# Sheet4.net
KiCad netlist of a schematic drawn in Altium Designer
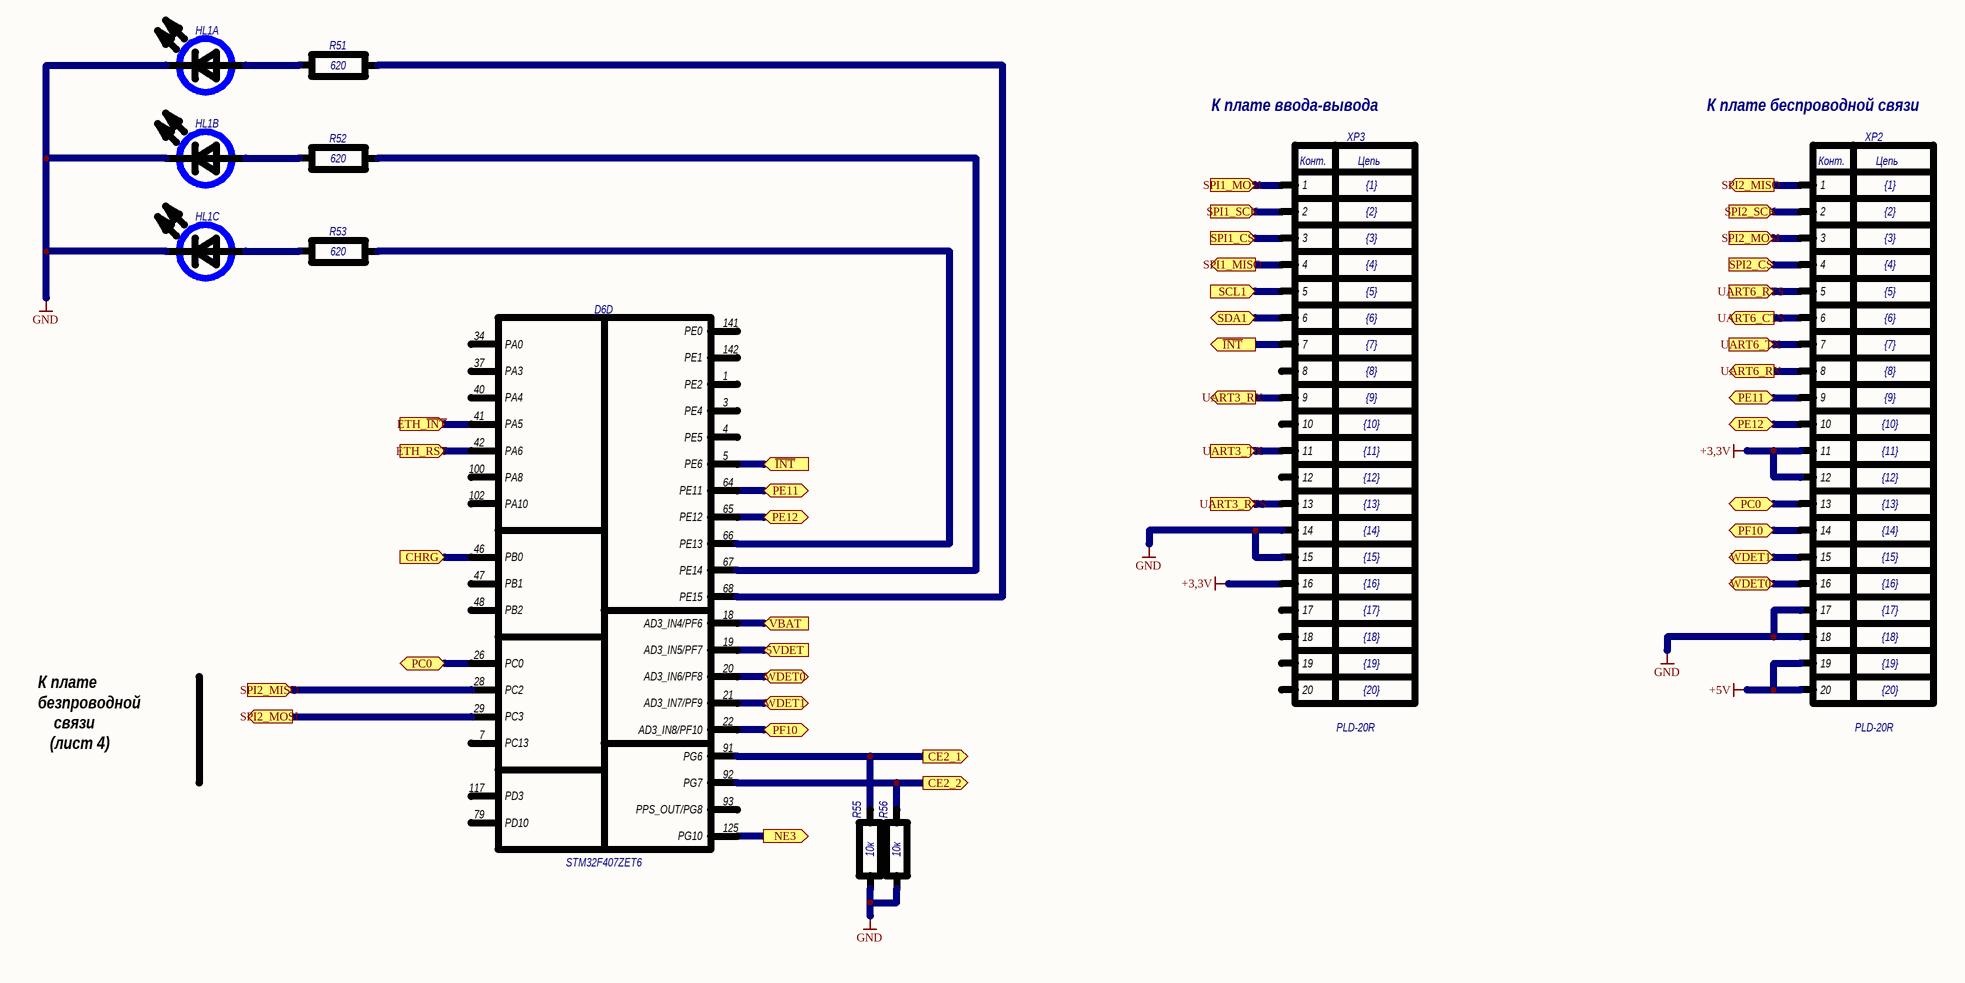
[diagram p0: Sheet4.SCHDOC]

(export (version "E")
  (design (tool "Eeschema 10.0.6"))
  (components
    (comp (ref "D6")
      (value "STM32F407ZET6")
      (footprint "LQFP-144")
      (libsource (lib "*") (part "STM32F407ZET6"))
    )
    (comp (ref "HL1")
      (value "L-7104SA-3GD")
      (footprint "L-7104SA-3GD")
      (description "{Description}")
      (libsource (lib "") (part "L-7104SA-3GD_1"))
    )
    (comp (ref "R51")
      (value "620")
      (footprint "0805")
      (description "РЕЗИСТОР")
      (fields (field (name "Comment") "Р0805"))
      (libsource (lib "*") (part "Р0805"))
    )
    (comp (ref "R52")
      (value "620")
      (footprint "0805")
      (description "РЕЗИСТОР")
      (fields (field (name "Comment") "Р0805"))
      (libsource (lib "*") (part "Р0805"))
    )
    (comp (ref "R53")
      (value "620")
      (footprint "0805")
      (description "РЕЗИСТОР")
      (fields (field (name "Comment") "Р0805"))
      (libsource (lib "*") (part "Р0805"))
    )
    (comp (ref "R55")
      (value "Р0805")
      (footprint "0805")
      (description "РЕЗИСТОР")
      (fields (field (name "ALTIUM_UNNAMED_1") "10к"))
      (libsource (lib "*") (part "Р0805"))
    )
    (comp (ref "R56")
      (value "Р0805")
      (footprint "0805")
      (description "РЕЗИСТОР")
      (fields (field (name "ALTIUM_UNNAMED_1") "10к"))
      (libsource (lib "*") (part "Р0805"))
    )
    (comp (ref "XP2")
      (value "PLD-20R")
      (footprint "PLD-20R")
      (description "{Description}")
      (fields
        (field (name "18") "{18}")
        (field (name "15") "{15}")
        (field (name "12") "{12}")
        (field (name "9") "{9}")
        (field (name "6") "{6}")
        (field (name "3") "{3}")
        (field (name "1") "{1}")
        (field (name "19") "{19}")
        (field (name "16") "{16}")
        (field (name "20") "{20}")
        (field (name "17") "{17}")
        (field (name "13") "{13}")
        (field (name "10") "{10}")
        (field (name "14") "{14}")
        (field (name "11") "{11}")
        (field (name "7") "{7}")
        (field (name "4") "{4}")
        (field (name "8") "{8}")
        (field (name "5") "{5}")
        (field (name "2") "{2}")
      )
      (libsource (lib "*") (part "PLD-20R"))
    )
    (comp (ref "XP3")
      (value "PLD-20R")
      (footprint "PLD-20R")
      (description "{Description}")
      (fields
        (field (name "18") "{18}")
        (field (name "15") "{15}")
        (field (name "12") "{12}")
        (field (name "9") "{9}")
        (field (name "6") "{6}")
        (field (name "3") "{3}")
        (field (name "1") "{1}")
        (field (name "19") "{19}")
        (field (name "16") "{16}")
        (field (name "20") "{20}")
        (field (name "17") "{17}")
        (field (name "13") "{13}")
        (field (name "10") "{10}")
        (field (name "14") "{14}")
        (field (name "11") "{11}")
        (field (name "7") "{7}")
        (field (name "4") "{4}")
        (field (name "8") "{8}")
        (field (name "5") "{5}")
        (field (name "2") "{2}")
      )
      (libsource (lib "*") (part "PLD-20R"))
    )
  )
  (nets
    (net (code "1") (name "+3,3V") (class "Default")
      (node (ref "XP2") (pin "11") (pinfunction "11_11") (pintype "passive"))
      (node (ref "XP2") (pin "12") (pinfunction "12_12") (pintype "passive"))
      (node (ref "XP3") (pin "16") (pinfunction "16_16") (pintype "passive"))
    )
    (net (code "2") (name "+5V") (class "Default")
      (node (ref "XP2") (pin "19") (pinfunction "19_19") (pintype "passive"))
      (node (ref "XP2") (pin "20") (pinfunction "20_20") (pintype "passive"))
    )
    (net (code "3") (name "/5VDET") (class "Default")
      (node (ref "D6") (pin "19") (pinfunction "AD3_IN5/PF7_19") (pintype "passive"))
    )
    (net (code "4") (name "/CE2_1") (class "Default")
      (node (ref "D6") (pin "91") (pinfunction "PG6_91") (pintype "passive"))
      (node (ref "R55") (pin "2") (pinfunction "2_2") (pintype "passive"))
    )
    (net (code "5") (name "/CE2_2") (class "Default")
      (node (ref "D6") (pin "92") (pinfunction "PG7_92") (pintype "passive"))
      (node (ref "R56") (pin "2") (pinfunction "2_2") (pintype "passive"))
    )
    (net (code "6") (name "/CHRG") (class "Default")
      (node (ref "D6") (pin "46") (pinfunction "PB0_46") (pintype "passive"))
    )
    (net (code "7") (name "/ETH_RST") (class "Default")
      (node (ref "D6") (pin "42") (pinfunction "PA6_42") (pintype "passive"))
    )
    (net (code "8") (name "/ETH_~{INT}") (class "Default")
      (node (ref "D6") (pin "41") (pinfunction "PA5_41") (pintype "passive"))
    )
    (net (code "9") (name "/NE3") (class "Default")
      (node (ref "D6") (pin "125") (pinfunction "PG10_125") (pintype "passive"))
    )
    (net (code "10") (name "/PC0") (class "Default")
      (node (ref "D6") (pin "26") (pinfunction "PC0_26") (pintype "passive"))
      (node (ref "XP2") (pin "13") (pinfunction "13_13") (pintype "passive"))
    )
    (net (code "11") (name "/PE11") (class "Default")
      (node (ref "D6") (pin "64") (pinfunction "PE11_64") (pintype "passive"))
      (node (ref "XP2") (pin "9") (pinfunction "9_9") (pintype "passive"))
    )
    (net (code "12") (name "/PE12") (class "Default")
      (node (ref "D6") (pin "65") (pinfunction "PE12_65") (pintype "passive"))
      (node (ref "XP2") (pin "10") (pinfunction "10_10") (pintype "passive"))
    )
    (net (code "13") (name "/PF10") (class "Default")
      (node (ref "D6") (pin "22") (pinfunction "AD3_IN8/PF10_22") (pintype "passive"))
      (node (ref "XP2") (pin "14") (pinfunction "14_14") (pintype "passive"))
    )
    (net (code "14") (name "/SCL1") (class "Default")
      (node (ref "XP3") (pin "5") (pinfunction "5_5") (pintype "passive"))
    )
    (net (code "15") (name "/SDA1") (class "Default")
      (node (ref "XP3") (pin "6") (pinfunction "6_6") (pintype "passive"))
    )
    (net (code "16") (name "/SPI1_CS") (class "Default")
      (node (ref "XP3") (pin "3") (pinfunction "3_3") (pintype "passive"))
    )
    (net (code "17") (name "/SPI1_MISO") (class "Default")
      (node (ref "XP3") (pin "4") (pinfunction "4_4") (pintype "passive"))
    )
    (net (code "18") (name "/SPI1_MOSI") (class "Default")
      (node (ref "XP3") (pin "1") (pinfunction "1_1") (pintype "passive"))
    )
    (net (code "19") (name "/SPI1_SCK") (class "Default")
      (node (ref "XP3") (pin "2") (pinfunction "2_2") (pintype "passive"))
    )
    (net (code "20") (name "/SPI2_CS") (class "Default")
      (node (ref "XP2") (pin "4") (pinfunction "4_4") (pintype "passive"))
    )
    (net (code "21") (name "/SPI2_MISO") (class "Default")
      (node (ref "D6") (pin "28") (pinfunction "PC2_28") (pintype "passive"))
      (node (ref "XP2") (pin "1") (pinfunction "1_1") (pintype "passive"))
    )
    (net (code "22") (name "/SPI2_MOSI") (class "Default")
      (node (ref "D6") (pin "29") (pinfunction "PC3_29") (pintype "passive"))
      (node (ref "XP2") (pin "3") (pinfunction "3_3") (pintype "passive"))
    )
    (net (code "23") (name "/SPI2_SCK") (class "Default")
      (node (ref "XP2") (pin "2") (pinfunction "2_2") (pintype "passive"))
    )
    (net (code "24") (name "/UART3_RTS") (class "Default")
      (node (ref "XP3") (pin "13") (pinfunction "13_13") (pintype "passive"))
    )
    (net (code "25") (name "/UART3_RX") (class "Default")
      (node (ref "XP3") (pin "9") (pinfunction "9_9") (pintype "passive"))
    )
    (net (code "26") (name "/UART3_TX") (class "Default")
      (node (ref "XP3") (pin "11") (pinfunction "11_11") (pintype "passive"))
    )
    (net (code "27") (name "/UART6_CTS") (class "Default")
      (node (ref "XP2") (pin "6") (pinfunction "6_6") (pintype "passive"))
    )
    (net (code "28") (name "/UART6_RTS") (class "Default")
      (node (ref "XP2") (pin "5") (pinfunction "5_5") (pintype "passive"))
    )
    (net (code "29") (name "/UART6_RX") (class "Default")
      (node (ref "XP2") (pin "8") (pinfunction "8_8") (pintype "passive"))
    )
    (net (code "30") (name "/UART6_TX") (class "Default")
      (node (ref "XP2") (pin "7") (pinfunction "7_7") (pintype "passive"))
    )
    (net (code "31") (name "/VBAT") (class "Default")
      (node (ref "D6") (pin "18") (pinfunction "AD3_IN4/PF6_18") (pintype "passive"))
    )
    (net (code "32") (name "/WDET0") (class "Default")
      (node (ref "D6") (pin "20") (pinfunction "AD3_IN6/PF8_20") (pintype "passive"))
      (node (ref "XP2") (pin "16") (pinfunction "16_16") (pintype "passive"))
    )
    (net (code "33") (name "/WDET1") (class "Default")
      (node (ref "D6") (pin "21") (pinfunction "AD3_IN7/PF9_21") (pintype "passive"))
      (node (ref "XP2") (pin "15") (pinfunction "15_15") (pintype "passive"))
    )
    (net (code "34") (name "/~{INT}") (class "Default")
      (node (ref "D6") (pin "5") (pinfunction "PE6_5") (pintype "passive"))
      (node (ref "XP3") (pin "7") (pinfunction "7_7") (pintype "passive"))
    )
    (net (code "35") (name "GND") (class "Default")
      (node (ref "HL1") (pin "2") (pinfunction "2_2") (pintype "passive"))
      (node (ref "HL1") (pin "4") (pinfunction "2_4") (pintype "passive"))
      (node (ref "HL1") (pin "6") (pinfunction "2_6") (pintype "passive"))
      (node (ref "R55") (pin "1") (pinfunction "1_1") (pintype "passive"))
      (node (ref "R56") (pin "1") (pinfunction "1_1") (pintype "passive"))
      (node (ref "XP2") (pin "17") (pinfunction "17_17") (pintype "passive"))
      (node (ref "XP2") (pin "18") (pinfunction "18_18") (pintype "passive"))
      (node (ref "XP3") (pin "14") (pinfunction "14_14") (pintype "passive"))
      (node (ref "XP3") (pin "15") (pinfunction "15_15") (pintype "passive"))
    )
    (net (code "36") (name "Net-(D6D-PE13)") (class "Default")
      (node (ref "D6") (pin "66") (pinfunction "PE13_66") (pintype "passive"))
      (node (ref "R53") (pin "2") (pinfunction "2_2") (pintype "passive"))
    )
    (net (code "37") (name "Net-(D6D-PE14)") (class "Default")
      (node (ref "D6") (pin "67") (pinfunction "PE14_67") (pintype "passive"))
      (node (ref "R52") (pin "2") (pinfunction "2_2") (pintype "passive"))
    )
    (net (code "38") (name "Net-(D6D-PE15)") (class "Default")
      (node (ref "D6") (pin "68") (pinfunction "PE15_68") (pintype "passive"))
      (node (ref "R51") (pin "2") (pinfunction "2_2") (pintype "passive"))
    )
    (net (code "39") (name "Net-(HL1-Pad1)") (class "Default")
      (node (ref "HL1") (pin "1") (pinfunction "1_1") (pintype "passive"))
      (node (ref "R51") (pin "1") (pinfunction "1_1") (pintype "passive"))
    )
    (net (code "40") (name "Net-(HL1B-1)") (class "Default")
      (node (ref "HL1") (pin "3") (pinfunction "1_3") (pintype "passive"))
      (node (ref "R52") (pin "1") (pinfunction "1_1") (pintype "passive"))
    )
    (net (code "41") (name "Net-(HL1C-1)") (class "Default")
      (node (ref "HL1") (pin "5") (pinfunction "1_5") (pintype "passive"))
      (node (ref "R53") (pin "1") (pinfunction "1_1") (pintype "passive"))
    )
    (net (code "42") (name "unconnected-(D6-Pad49)") (class "Default")
      (node (ref "D6") (pin "49") (pintype "passive"))
    )
    (net (code "43") (name "unconnected-(D6D-PA0-Pad34)") (class "Default")
      (node (ref "D6") (pin "34") (pinfunction "PA0_34") (pintype "passive"))
    )
    (net (code "44") (name "unconnected-(D6D-PA3-Pad37)") (class "Default")
      (node (ref "D6") (pin "37") (pinfunction "PA3_37") (pintype "passive"))
    )
    (net (code "45") (name "unconnected-(D6D-PA4-Pad40)") (class "Default")
      (node (ref "D6") (pin "40") (pinfunction "PA4_40") (pintype "passive"))
    )
    (net (code "46") (name "unconnected-(D6D-PA8-Pad100)") (class "Default")
      (node (ref "D6") (pin "100") (pinfunction "PA8_100") (pintype "passive"))
    )
    (net (code "47") (name "unconnected-(D6D-PA10-Pad102)") (class "Default")
      (node (ref "D6") (pin "102") (pinfunction "PA10_102") (pintype "passive"))
    )
    (net (code "48") (name "unconnected-(D6D-PB1-Pad47)") (class "Default")
      (node (ref "D6") (pin "47") (pinfunction "PB1_47") (pintype "passive"))
    )
    (net (code "49") (name "unconnected-(D6D-PB2-Pad48)") (class "Default")
      (node (ref "D6") (pin "48") (pinfunction "PB2_48") (pintype "passive"))
    )
    (net (code "50") (name "unconnected-(D6D-PC13-Pad7)") (class "Default")
      (node (ref "D6") (pin "7") (pinfunction "PC13_7") (pintype "passive"))
    )
    (net (code "51") (name "unconnected-(D6D-PD3-Pad117)") (class "Default")
      (node (ref "D6") (pin "117") (pinfunction "PD3_117") (pintype "passive"))
    )
    (net (code "52") (name "unconnected-(D6D-PD10-Pad79)") (class "Default")
      (node (ref "D6") (pin "79") (pinfunction "PD10_79") (pintype "passive"))
    )
    (net (code "53") (name "unconnected-(D6D-PE0-Pad141)") (class "Default")
      (node (ref "D6") (pin "141") (pinfunction "PE0_141") (pintype "passive"))
    )
    (net (code "54") (name "unconnected-(D6D-PE1-Pad142)") (class "Default")
      (node (ref "D6") (pin "142") (pinfunction "PE1_142") (pintype "passive"))
    )
    (net (code "55") (name "unconnected-(D6D-PE2-Pad1)") (class "Default")
      (node (ref "D6") (pin "1") (pinfunction "PE2_1") (pintype "passive"))
    )
    (net (code "56") (name "unconnected-(D6D-PE4-Pad3)") (class "Default")
      (node (ref "D6") (pin "3") (pinfunction "PE4_3") (pintype "passive"))
    )
    (net (code "57") (name "unconnected-(D6D-PE5-Pad4)") (class "Default")
      (node (ref "D6") (pin "4") (pinfunction "PE5_4") (pintype "passive"))
    )
    (net (code "58") (name "unconnected-(D6D-PPS_OUT{slash}PG8-Pad93)") (class "Default")
      (node (ref "D6") (pin "93") (pinfunction "PPS_OUT/PG8_93") (pintype "passive"))
    )
    (net (code "59") (name "unconnected-(XP3-Pad8)") (class "Default")
      (node (ref "XP3") (pin "8") (pinfunction "8_8") (pintype "passive"))
    )
    (net (code "60") (name "unconnected-(XP3-Pad10)") (class "Default")
      (node (ref "XP3") (pin "10") (pinfunction "10_10") (pintype "passive"))
    )
    (net (code "61") (name "unconnected-(XP3-Pad12)") (class "Default")
      (node (ref "XP3") (pin "12") (pinfunction "12_12") (pintype "passive"))
    )
    (net (code "62") (name "unconnected-(XP3-Pad17)") (class "Default")
      (node (ref "XP3") (pin "17") (pinfunction "17_17") (pintype "passive"))
    )
    (net (code "63") (name "unconnected-(XP3-Pad18)") (class "Default")
      (node (ref "XP3") (pin "18") (pinfunction "18_18") (pintype "passive"))
    )
    (net (code "64") (name "unconnected-(XP3-Pad19)") (class "Default")
      (node (ref "XP3") (pin "19") (pinfunction "19_19") (pintype "passive"))
    )
    (net (code "65") (name "unconnected-(XP3-Pad20)") (class "Default")
      (node (ref "XP3") (pin "20") (pinfunction "20_20") (pintype "passive"))
    )
  )
)
